# navi.net
KiCad netlist of a schematic drawn in EAGLE
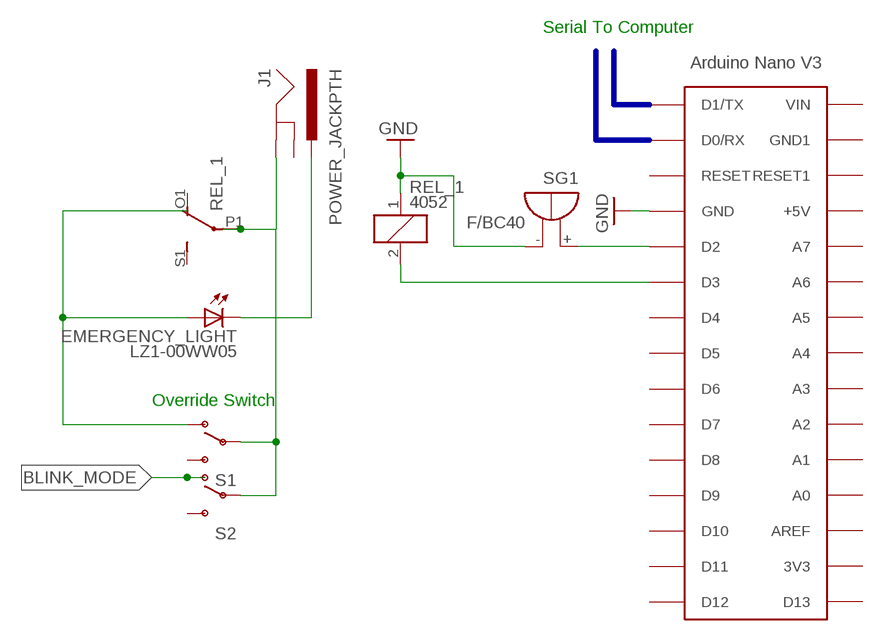
[diagram p0: schematic, sheet 1]

(export (version "E")
  (design (tool "Eeschema 10.0.6"))
  (components
    (comp (ref "EMERGENCY_LIGHT")
      (value "LZ1-00WW05")
      (footprint "eagle-import:LZ1-00WW03")
      (libsource (lib "eagle-import") (part "LZ1-00WW05"))
    )
    (comp (ref "J1")
      (value "POWER_JACKPTH")
      (footprint "eagle-import:POWER_JACK_PTH")
      (libsource (lib "eagle-import") (part "POWER_JACKPTH"))
    )
    (comp (ref "REL_1")
      (value "4052")
      (footprint "eagle-import:F4052")
      (libsource (lib "eagle-import") (part "4052"))
    )
    (comp (ref "S1")
      (value "SWITCH-SPDTKIT")
      (footprint "eagle-import:SWITCH-SPDT_KIT")
      (libsource (lib "eagle-import") (part "SWITCH-SPDTKIT"))
    )
    (comp (ref "S2")
      (value "SWITCH-SPDTKIT")
      (footprint "eagle-import:SWITCH-SPDT_KIT")
      (libsource (lib "eagle-import") (part "SWITCH-SPDTKIT"))
    )
    (comp (ref "SG1")
      (value "F/BC40")
      (footprint "eagle-import:F_BC40")
      (libsource (lib "eagle-import") (part "F/BC40"))
    )
    (comp (ref "U$1")
      (value "ARDUINONANO")
      (footprint "eagle-import:PDIP-32")
      (libsource (lib "eagle-import") (part "ARDUINONANO"))
    )
  )
  (nets
    (net (code "1") (name "BLINK_MODE") (class "Default")
      (node (ref "S2") (pin "1") (pinfunction "O_1") (pintype "passive"))
    )
    (net (code "2") (name "GND") (class "Default")
      (node (ref "REL_1") (pin "1") (pinfunction "1_1") (pintype "passive"))
      (node (ref "SG1") (pin "-") (pinfunction "-_-") (pintype "passive"))
      (node (ref "U$1") (pin "GND") (pinfunction "GND_GND") (pintype "bidirectional"))
    )
    (net (code "3") (name "Net-(EMERGENCY_LIGHT-C-Pad1)") (class "Default")
      (node (ref "EMERGENCY_LIGHT") (pin "1") (pinfunction "C_1") (pintype "passive"))
      (node (ref "EMERGENCY_LIGHT") (pin "4") (pinfunction "C_4") (pintype "passive"))
      (node (ref "J1") (pin "PWR") (pinfunction "PWR_PWR") (pintype "bidirectional"))
    )
    (net (code "4") (name "Net-(REL_1-Pad2)") (class "Default")
      (node (ref "REL_1") (pin "2") (pinfunction "2_2") (pintype "passive"))
      (node (ref "U$1") (pin "D3") (pinfunction "D3_D3") (pintype "bidirectional"))
    )
    (net (code "5") (name "Net-(REL_1B-P)") (class "Default")
      (node (ref "J1") (pin "GND") (pinfunction "GND_GND") (pintype "bidirectional"))
      (node (ref "REL_1") (pin "P1") (pinfunction "P_P1") (pintype "passive"))
      (node (ref "S1") (pin "2") (pinfunction "P_2") (pintype "passive"))
      (node (ref "S2") (pin "2") (pinfunction "P_2") (pintype "passive"))
    )
    (net (code "6") (name "Net-(S1-O)") (class "Default")
      (node (ref "EMERGENCY_LIGHT") (pin "2") (pinfunction "A_2") (pintype "passive"))
      (node (ref "EMERGENCY_LIGHT") (pin "3") (pinfunction "A_3") (pintype "passive"))
      (node (ref "EMERGENCY_LIGHT") (pin "5") (pinfunction "A_5") (pintype "passive"))
      (node (ref "S1") (pin "1") (pinfunction "O_1") (pintype "passive"))
    )
    (net (code "7") (name "Net-(SG1-Pad+)") (class "Default")
      (node (ref "SG1") (pin "+") (pinfunction "+_+") (pintype "passive"))
      (node (ref "U$1") (pin "D2") (pinfunction "D2_D2") (pintype "bidirectional"))
    )
    (net (code "8") (name "unconnected-(J1-PadGNDBREAK)") (class "Default")
      (node (ref "J1") (pin "GNDBREAK") (pinfunction "GNDBREAK_GNDBREAK") (pintype "bidirectional"))
    )
    (net (code "9") (name "unconnected-(REL_1B-O-PadO1)") (class "Default")
      (node (ref "REL_1") (pin "O1") (pinfunction "O_O1") (pintype "passive"))
    )
    (net (code "10") (name "unconnected-(REL_1B-S-PadS1)") (class "Default")
      (node (ref "REL_1") (pin "S1") (pinfunction "S_S1") (pintype "passive"))
    )
    (net (code "11") (name "unconnected-(S1-S-Pad3)") (class "Default")
      (node (ref "S1") (pin "3") (pinfunction "S_3") (pintype "passive"))
    )
    (net (code "12") (name "unconnected-(S2-S-Pad3)") (class "Default")
      (node (ref "S2") (pin "3") (pinfunction "S_3") (pintype "passive"))
    )
    (net (code "13") (name "unconnected-(U$1-A0-PadA7)") (class "Default")
      (node (ref "U$1") (pin "A7") (pinfunction "A0_A7") (pintype "bidirectional"))
    )
    (net (code "14") (name "unconnected-(U$1-A1-PadA6)") (class "Default")
      (node (ref "U$1") (pin "A6") (pinfunction "A1_A6") (pintype "bidirectional"))
    )
    (net (code "15") (name "unconnected-(U$1-A2-PadA5)") (class "Default")
      (node (ref "U$1") (pin "A5") (pinfunction "A2_A5") (pintype "bidirectional"))
    )
    (net (code "16") (name "unconnected-(U$1-A3-PadA4)") (class "Default")
      (node (ref "U$1") (pin "A4") (pinfunction "A3_A4") (pintype "bidirectional"))
    )
    (net (code "17") (name "unconnected-(U$1-A4-PadA3)") (class "Default")
      (node (ref "U$1") (pin "A3") (pinfunction "A4_A3") (pintype "bidirectional"))
    )
    (net (code "18") (name "unconnected-(U$1-A5-PadA2)") (class "Default")
      (node (ref "U$1") (pin "A2") (pinfunction "A5_A2") (pintype "bidirectional"))
    )
    (net (code "19") (name "unconnected-(U$1-A6-PadA1)") (class "Default")
      (node (ref "U$1") (pin "A1") (pinfunction "A6_A1") (pintype "bidirectional"))
    )
    (net (code "20") (name "unconnected-(U$1-A7-PadA0)") (class "Default")
      (node (ref "U$1") (pin "A0") (pinfunction "A7_A0") (pintype "bidirectional"))
    )
    (net (code "21") (name "unconnected-(U$1-Pad+5V)") (class "Default")
      (node (ref "U$1") (pin "+5V") (pinfunction "+5V_+5V") (pintype "bidirectional"))
    )
    (net (code "22") (name "unconnected-(U$1-Pad3V3)") (class "Default")
      (node (ref "U$1") (pin "3V3") (pinfunction "3V3_3V3") (pintype "bidirectional"))
    )
    (net (code "23") (name "unconnected-(U$1-PadAREF)") (class "Default")
      (node (ref "U$1") (pin "AREF") (pinfunction "AREF_AREF") (pintype "bidirectional"))
    )
    (net (code "24") (name "unconnected-(U$1-PadD0{slash}RX)") (class "Default")
      (node (ref "U$1") (pin "D0/RX") (pinfunction "D0/RX_D0/RX") (pintype "bidirectional"))
    )
    (net (code "25") (name "unconnected-(U$1-PadD1{slash}TX)") (class "Default")
      (node (ref "U$1") (pin "D1/TX") (pinfunction "D1/TX_D1/TX") (pintype "bidirectional"))
    )
    (net (code "26") (name "unconnected-(U$1-PadD4)") (class "Default")
      (node (ref "U$1") (pin "D4") (pinfunction "D4_D4") (pintype "bidirectional"))
    )
    (net (code "27") (name "unconnected-(U$1-PadD5)") (class "Default")
      (node (ref "U$1") (pin "D5") (pinfunction "D5_D5") (pintype "bidirectional"))
    )
    (net (code "28") (name "unconnected-(U$1-PadD6)") (class "Default")
      (node (ref "U$1") (pin "D6") (pinfunction "D6_D6") (pintype "bidirectional"))
    )
    (net (code "29") (name "unconnected-(U$1-PadD7)") (class "Default")
      (node (ref "U$1") (pin "D7") (pinfunction "D7_D7") (pintype "bidirectional"))
    )
    (net (code "30") (name "unconnected-(U$1-PadD8)") (class "Default")
      (node (ref "U$1") (pin "D8") (pinfunction "D8_D8") (pintype "bidirectional"))
    )
    (net (code "31") (name "unconnected-(U$1-PadD9)") (class "Default")
      (node (ref "U$1") (pin "D9") (pinfunction "D9_D9") (pintype "bidirectional"))
    )
    (net (code "32") (name "unconnected-(U$1-PadD10)") (class "Default")
      (node (ref "U$1") (pin "D10") (pinfunction "D10_D10") (pintype "bidirectional"))
    )
    (net (code "33") (name "unconnected-(U$1-PadD11)") (class "Default")
      (node (ref "U$1") (pin "D11") (pinfunction "D11_D11") (pintype "bidirectional"))
    )
    (net (code "34") (name "unconnected-(U$1-PadD12)") (class "Default")
      (node (ref "U$1") (pin "D12") (pinfunction "D12_D12") (pintype "bidirectional"))
    )
    (net (code "35") (name "unconnected-(U$1-PadD13)") (class "Default")
      (node (ref "U$1") (pin "D13") (pinfunction "D13_D13") (pintype "bidirectional"))
    )
    (net (code "36") (name "unconnected-(U$1-PadGND1)") (class "Default")
      (node (ref "U$1") (pin "GND1") (pinfunction "GND1_GND1") (pintype "bidirectional"))
    )
    (net (code "37") (name "unconnected-(U$1-PadRESET)") (class "Default")
      (node (ref "U$1") (pin "RESET") (pinfunction "RESET_RESET") (pintype "bidirectional"))
    )
    (net (code "38") (name "unconnected-(U$1-PadRESET1)") (class "Default")
      (node (ref "U$1") (pin "RESET1") (pinfunction "RESET1_RESET1") (pintype "bidirectional"))
    )
    (net (code "39") (name "unconnected-(U$1-PadVIN)") (class "Default")
      (node (ref "U$1") (pin "VIN") (pinfunction "VIN_VIN") (pintype "bidirectional"))
    )
  )
)
